# CAN_3V3.net
KiCad netlist of a schematic drawn in Altium Designer
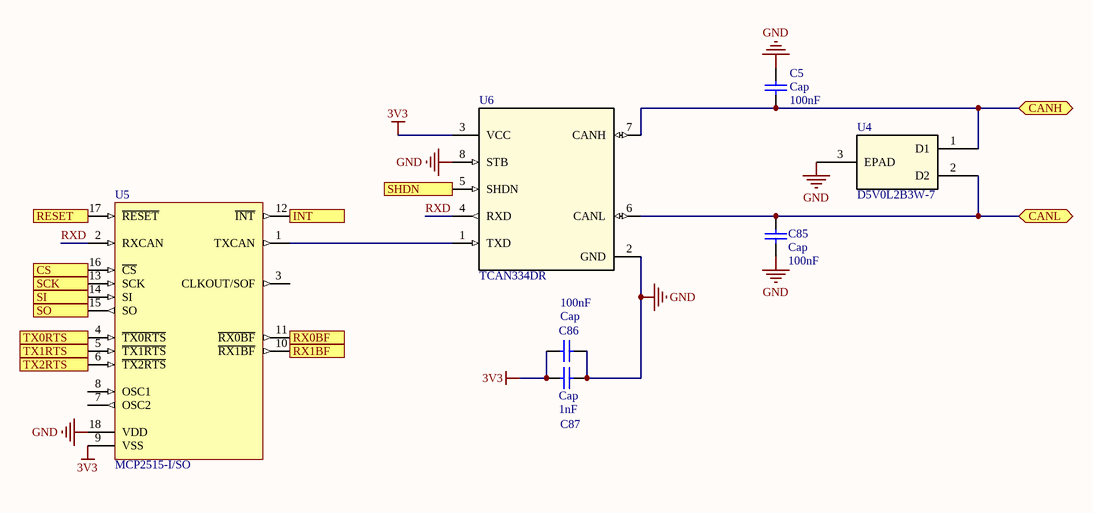
[diagram p0: CAN 3V3.SchDoc]

(export (version "E")
  (design (tool "Eeschema 10.0.6"))
  (components
    (comp (ref "C5")
      (value "Cap")
      (footprint "1608[0603]")
      (description "Capacitor")
      (fields (field (name "ALTIUM_VALUE") "100nF") (field (name "PUBLISHER") "Altium Limited"))
      (libsource (lib "Miscellaneous Devices") (part "Cap"))
    )
    (comp (ref "C85")
      (value "Cap")
      (footprint "1608[0603]")
      (description "Capacitor")
      (fields (field (name "ALTIUM_VALUE") "100nF") (field (name "PUBLISHER") "Altium Limited"))
      (libsource (lib "Miscellaneous Devices") (part "Cap"))
    )
    (comp (ref "C86")
      (value "Cap")
      (footprint "1608[0603]")
      (description "Capacitor")
      (fields (field (name "ALTIUM_VALUE") "100nF") (field (name "PUBLISHER") "Altium Limited"))
      (libsource (lib "Miscellaneous Devices") (part "Cap"))
    )
    (comp (ref "C87")
      (value "Cap")
      (footprint "1608[0603]")
      (description "Capacitor")
      (fields (field (name "ALTIUM_VALUE") "1nF") (field (name "PUBLISHER") "Altium Limited"))
      (libsource (lib "Miscellaneous Devices") (part "Cap"))
    )
    (comp (ref "U4")
      (value "D5V0L2B3W-7")
      (footprint "SOT-323_DIO")
      (description "No Description Available")
      (fields (field (name "COPYRIGHT") "Copyright (C) 2018 Accelerated Designs. All rights reserved"))
      (libsource (lib "D5V0L2B3W-7 library") (part "D5V0L2B3W-7"))
    )
    (comp (ref "U5")
      (value "MCP2515-I/SO")
      (footprint "SOIC-SO18_L")
      (description "Stand-Alone CAN Controller With SPI Interface, 18-Pin SOIC, Industrial Temperature")
      (libsource (lib "Altium Content Vault") (part "COM-CAN-MCP2515-18"))
    )
    (comp (ref "U6")
      (value "TCAN334DR")
      (footprint "D0008A_N")
      (description "No Description Available")
      (fields
        (field (name "MANUFACTURER") "Texas Instruments")
        (field (name "COPYRIGHT") "Copyright (C) 2018 Accelerated Designs. All rights reserved")
      )
      (libsource (lib "CANTRAN3V3") (part "TCAN334DR"))
    )
  )
  (nets
    (net (code "1") (name "/CANH") (class "Default")
      (node (ref "C5") (pin "2") (pinfunction "2_2") (pintype "passive"))
      (node (ref "U4") (pin "1") (pinfunction "D1_1") (pintype "passive"))
      (node (ref "U6") (pin "7") (pinfunction "CANH_7") (pintype "bidirectional"))
    )
    (net (code "2") (name "/CANL") (class "Default")
      (node (ref "C85") (pin "2") (pinfunction "2_2") (pintype "passive"))
      (node (ref "U4") (pin "2") (pinfunction "D2_2") (pintype "passive"))
      (node (ref "U6") (pin "6") (pinfunction "CANL_6") (pintype "bidirectional"))
    )
    (net (code "3") (name "/CS") (class "Default")
      (node (ref "U5") (pin "16") (pinfunction "~{CS}_16") (pintype "input"))
    )
    (net (code "4") (name "/INT") (class "Default")
      (node (ref "U5") (pin "12") (pinfunction "~{INT}_12") (pintype "output"))
    )
    (net (code "5") (name "/RESET") (class "Default")
      (node (ref "U5") (pin "17") (pinfunction "~{RESET}_17") (pintype "input"))
    )
    (net (code "6") (name "/RX0BF") (class "Default")
      (node (ref "U5") (pin "11") (pinfunction "~{RX0BF}_11") (pintype "output"))
    )
    (net (code "7") (name "/RX1BF") (class "Default")
      (node (ref "U5") (pin "10") (pinfunction "~{RX1BF}_10") (pintype "output"))
    )
    (net (code "8") (name "/RXD") (class "Default")
      (node (ref "U5") (pin "2") (pinfunction "RXCAN_2") (pintype "input"))
      (node (ref "U6") (pin "4") (pinfunction "RXD_4") (pintype "output"))
    )
    (net (code "9") (name "/SCK") (class "Default")
      (node (ref "U5") (pin "13") (pinfunction "SCK_13") (pintype "input"))
    )
    (net (code "10") (name "/SHDN") (class "Default")
      (node (ref "U6") (pin "5") (pinfunction "SHDN_5") (pintype "input"))
    )
    (net (code "11") (name "/SI") (class "Default")
      (node (ref "U5") (pin "14") (pinfunction "SI_14") (pintype "input"))
    )
    (net (code "12") (name "/SO") (class "Default")
      (node (ref "U5") (pin "15") (pinfunction "SO_15") (pintype "output"))
    )
    (net (code "13") (name "/TX0RTS") (class "Default")
      (node (ref "U5") (pin "4") (pinfunction "~{TX0RTS}_4") (pintype "input"))
    )
    (net (code "14") (name "/TX1RTS") (class "Default")
      (node (ref "U5") (pin "5") (pinfunction "~{TX1RTS}_5") (pintype "input"))
    )
    (net (code "15") (name "/TX2RTS") (class "Default")
      (node (ref "U5") (pin "6") (pinfunction "~{TX2RTS}_6") (pintype "input"))
    )
    (net (code "16") (name "3V3") (class "Default")
      (node (ref "C86") (pin "1") (pinfunction "1_1") (pintype "passive"))
      (node (ref "C87") (pin "2") (pinfunction "2_2") (pintype "passive"))
      (node (ref "U5") (pin "9") (pinfunction "VSS_9") (pintype "power_in"))
      (node (ref "U6") (pin "3") (pinfunction "VCC_3") (pintype "power_in"))
    )
    (net (code "17") (name "GND") (class "Default")
      (node (ref "C5") (pin "1") (pinfunction "1_1") (pintype "passive"))
      (node (ref "C85") (pin "1") (pinfunction "1_1") (pintype "passive"))
      (node (ref "C86") (pin "2") (pinfunction "2_2") (pintype "passive"))
      (node (ref "C87") (pin "1") (pinfunction "1_1") (pintype "passive"))
      (node (ref "U4") (pin "3") (pinfunction "EPAD_3") (pintype "passive"))
      (node (ref "U5") (pin "18") (pinfunction "VDD_18") (pintype "power_in"))
      (node (ref "U6") (pin "2") (pinfunction "GND_2") (pintype "power_in"))
      (node (ref "U6") (pin "8") (pinfunction "STB_8") (pintype "input"))
    )
    (net (code "18") (name "Net-(U5-TXCAN)") (class "Default")
      (node (ref "U5") (pin "1") (pinfunction "TXCAN_1") (pintype "output"))
      (node (ref "U6") (pin "1") (pinfunction "TXD_1") (pintype "input"))
    )
    (net (code "19") (name "unconnected-(U5-CLKOUT{slash}SOF-Pad3)") (class "Default")
      (node (ref "U5") (pin "3") (pinfunction "CLKOUT/SOF_3") (pintype "output"))
    )
    (net (code "20") (name "unconnected-(U5-OSC1-Pad8)") (class "Default")
      (node (ref "U5") (pin "8") (pinfunction "OSC1_8") (pintype "input"))
    )
    (net (code "21") (name "unconnected-(U5-OSC2-Pad7)") (class "Default")
      (node (ref "U5") (pin "7") (pinfunction "OSC2_7") (pintype "output"))
    )
  )
)
